# 3_Power.net
KiCad netlist of a schematic drawn in Altium Designer
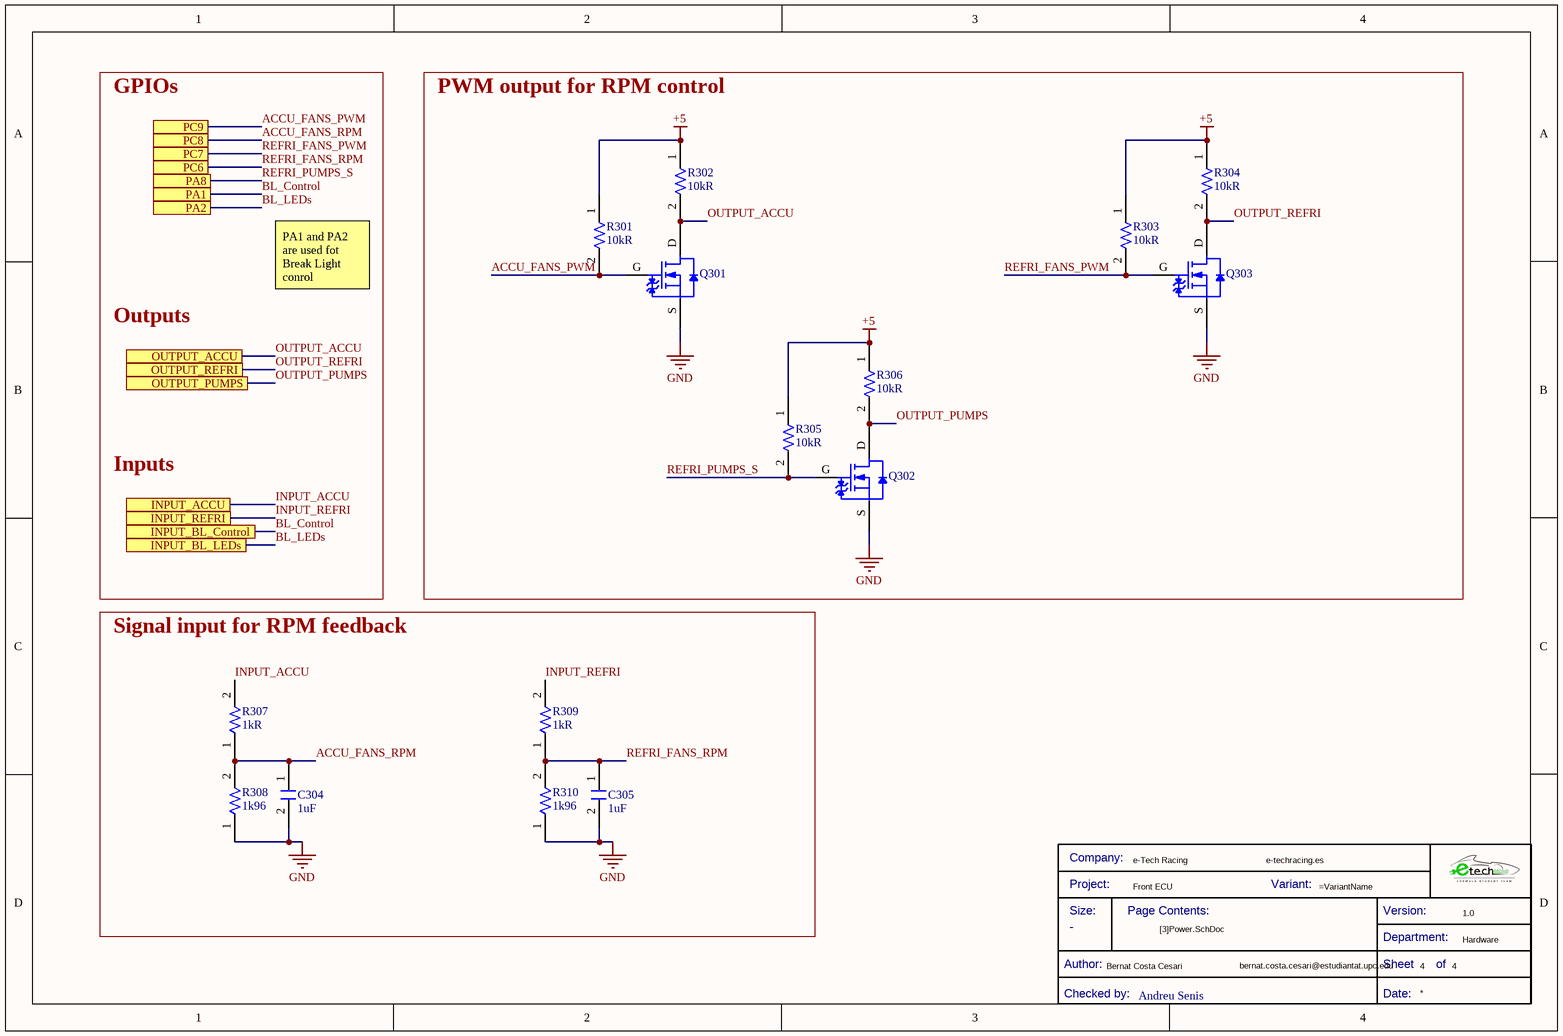
[diagram p0: [3]Power.SchDoc]

(export (version "E")
  (design (tool "Eeschema 10.0.6"))
  (components
    (comp (ref "C304")
      (value "885012207103")
      (footprint "C0805FNPC-R")
      (fields
        (field (name "TOLERANCE") "10%")
        (field (name "CAPACITANCE") "1uF")
        (field (name ".CREATOR") "GP")
      )
      (libsource (lib "Passives") (part "C1u-50V-0805FNPC-X7R"))
    )
    (comp (ref "C305")
      (value "885012207103")
      (footprint "C0805FNPC-R")
      (fields
        (field (name "TOLERANCE") "10%")
        (field (name "CAPACITANCE") "1uF")
        (field (name ".CREATOR") "GP")
      )
      (libsource (lib "Passives") (part "C1u-50V-0805FNPC-X7R"))
    )
    (comp (ref "Q301")
      (value "CPH3455-TL-H")
      (footprint "TRT-NCH-3/35-CPH")
      (description "CPH3455-TL-H N-channel MOSFET Transistor; 3 A; 35 V; 3-Pin CPH")
      (fields (field (name "MANUFACTURER") "ON Semiconductor") (field (name ".CREATOR") "GP"))
      (libsource (lib "Semiconductor") (part "TRT-NCH-3/35-CPH"))
    )
    (comp (ref "Q302")
      (value "CPH3455-TL-H")
      (footprint "TRT-NCH-3/35-CPH")
      (description "CPH3455-TL-H N-channel MOSFET Transistor; 3 A; 35 V; 3-Pin CPH")
      (fields (field (name "MANUFACTURER") "ON Semiconductor") (field (name ".CREATOR") "GP"))
      (libsource (lib "Semiconductor") (part "TRT-NCH-3/35-CPH"))
    )
    (comp (ref "Q303")
      (value "CPH3455-TL-H")
      (footprint "TRT-NCH-3/35-CPH")
      (description "CPH3455-TL-H N-channel MOSFET Transistor; 3 A; 35 V; 3-Pin CPH")
      (fields (field (name "MANUFACTURER") "ON Semiconductor") (field (name ".CREATOR") "GP"))
      (libsource (lib "Semiconductor") (part "TRT-NCH-3/35-CPH"))
    )
    (comp (ref "R301")
      (value "CR0805-JW-103ELF")
      (footprint "R0805FTK")
      (fields
        (field (name "TOLERANCE") "5%")
        (field (name "RESISTANCE") "10kR")
        (field (name ".CREATOR") "DR")
      )
      (libsource (lib "Passives") (part "R10k-0805FTK"))
    )
    (comp (ref "R302")
      (value "CR0805-JW-103ELF")
      (footprint "R0805FTK")
      (fields
        (field (name "TOLERANCE") "5%")
        (field (name "RESISTANCE") "10kR")
        (field (name ".CREATOR") "DR")
      )
      (libsource (lib "Passives") (part "R10k-0805FTK"))
    )
    (comp (ref "R303")
      (value "CR0805-JW-103ELF")
      (footprint "R0805FTK")
      (fields
        (field (name "TOLERANCE") "5%")
        (field (name "RESISTANCE") "10kR")
        (field (name ".CREATOR") "DR")
      )
      (libsource (lib "Passives") (part "R10k-0805FTK"))
    )
    (comp (ref "R304")
      (value "CR0805-JW-103ELF")
      (footprint "R0805FTK")
      (fields
        (field (name "TOLERANCE") "5%")
        (field (name "RESISTANCE") "10kR")
        (field (name ".CREATOR") "DR")
      )
      (libsource (lib "Passives") (part "R10k-0805FTK"))
    )
    (comp (ref "R305")
      (value "CR0805-JW-103ELF")
      (footprint "R0805FTK")
      (fields
        (field (name "TOLERANCE") "5%")
        (field (name "RESISTANCE") "10kR")
        (field (name ".CREATOR") "DR")
      )
      (libsource (lib "Passives") (part "R10k-0805FTK"))
    )
    (comp (ref "R306")
      (value "CR0805-JW-103ELF")
      (footprint "R0805FTK")
      (fields
        (field (name "TOLERANCE") "5%")
        (field (name "RESISTANCE") "10kR")
        (field (name ".CREATOR") "DR")
      )
      (libsource (lib "Passives") (part "R10k-0805FTK"))
    )
    (comp (ref "R307")
      (value "CR0805-JW-102ELF")
      (footprint "R0805FTK")
      (description "Res Thick Film 0805 1K Ohm 5% 1/8W ±200ppm/°C Molded SMD SMD Paper Tape on Plastic Reel")
      (fields
        (field (name "TOLERANCE") "5%")
        (field (name "RESISTANCE") "1kR")
        (field (name ".CREATOR") "GP")
      )
      (libsource (lib "Passives") (part "R1k-0805FTK"))
    )
    (comp (ref "R308")
      (value "1k96")
      (footprint "R0805FTK")
      (libsource (lib "Passives") (part "R1k96-0805FTK"))
    )
    (comp (ref "R309")
      (value "CR0805-JW-102ELF")
      (footprint "R0805FTK")
      (description "Res Thick Film 0805 1K Ohm 5% 1/8W ±200ppm/°C Molded SMD SMD Paper Tape on Plastic Reel")
      (fields
        (field (name "TOLERANCE") "5%")
        (field (name "RESISTANCE") "1kR")
        (field (name ".CREATOR") "GP")
      )
      (libsource (lib "Passives") (part "R1k-0805FTK"))
    )
    (comp (ref "R310")
      (value "1k96")
      (footprint "R0805FTK")
      (libsource (lib "Passives") (part "R1k96-0805FTK"))
    )
  )
  (nets
    (net (code "1") (name "+5") (class "Default")
      (node (ref "R301") (pin "1") (pinfunction "1_1") (pintype "passive"))
      (node (ref "R302") (pin "1") (pinfunction "1_1") (pintype "passive"))
      (node (ref "R303") (pin "1") (pinfunction "1_1") (pintype "passive"))
      (node (ref "R304") (pin "1") (pinfunction "1_1") (pintype "passive"))
      (node (ref "R305") (pin "1") (pinfunction "1_1") (pintype "passive"))
      (node (ref "R306") (pin "1") (pinfunction "1_1") (pintype "passive"))
    )
    (net (code "2") (name "/ACCU_FANS_PWM") (class "Default")
      (node (ref "Q301") (pin "G") (pinfunction "G_G") (pintype "passive"))
      (node (ref "R301") (pin "2") (pinfunction "2_2") (pintype "passive"))
    )
    (net (code "3") (name "/ACCU_FANS_RPM") (class "Default")
      (node (ref "C304") (pin "1") (pinfunction "1_1") (pintype "passive"))
      (node (ref "R307") (pin "1") (pinfunction "1_1") (pintype "passive"))
      (node (ref "R308") (pin "2") (pinfunction "2_2") (pintype "passive"))
    )
    (net (code "6") (name "/INPUT_ACCU") (class "Default")
      (node (ref "R307") (pin "2") (pinfunction "2_2") (pintype "passive"))
    )
    (net (code "7") (name "/INPUT_REFRI") (class "Default")
      (node (ref "R309") (pin "2") (pinfunction "2_2") (pintype "passive"))
    )
    (net (code "8") (name "/OUTPUT_ACCU") (class "Default")
      (node (ref "Q301") (pin "D") (pinfunction "D_D") (pintype "passive"))
      (node (ref "R302") (pin "2") (pinfunction "2_2") (pintype "passive"))
    )
    (net (code "9") (name "/OUTPUT_PUMPS") (class "Default")
      (node (ref "Q302") (pin "D") (pinfunction "D_D") (pintype "passive"))
      (node (ref "R306") (pin "2") (pinfunction "2_2") (pintype "passive"))
    )
    (net (code "10") (name "/OUTPUT_REFRI") (class "Default")
      (node (ref "Q303") (pin "D") (pinfunction "D_D") (pintype "passive"))
      (node (ref "R304") (pin "2") (pinfunction "2_2") (pintype "passive"))
    )
    (net (code "11") (name "/REFRI_FANS_PWM") (class "Default")
      (node (ref "Q303") (pin "G") (pinfunction "G_G") (pintype "passive"))
      (node (ref "R303") (pin "2") (pinfunction "2_2") (pintype "passive"))
    )
    (net (code "12") (name "/REFRI_FANS_RPM") (class "Default")
      (node (ref "C305") (pin "1") (pinfunction "1_1") (pintype "passive"))
      (node (ref "R309") (pin "1") (pinfunction "1_1") (pintype "passive"))
      (node (ref "R310") (pin "2") (pinfunction "2_2") (pintype "passive"))
    )
    (net (code "13") (name "/REFRI_PUMPS_S") (class "Default")
      (node (ref "Q302") (pin "G") (pinfunction "G_G") (pintype "passive"))
      (node (ref "R305") (pin "2") (pinfunction "2_2") (pintype "passive"))
    )
    (net (code "14") (name "GND") (class "Default")
      (node (ref "C304") (pin "2") (pinfunction "2_2") (pintype "passive"))
      (node (ref "C305") (pin "2") (pinfunction "2_2") (pintype "passive"))
      (node (ref "Q301") (pin "S") (pinfunction "S_S") (pintype "passive"))
      (node (ref "Q302") (pin "S") (pinfunction "S_S") (pintype "passive"))
      (node (ref "Q303") (pin "S") (pinfunction "S_S") (pintype "passive"))
      (node (ref "R308") (pin "1") (pinfunction "1_1") (pintype "passive"))
      (node (ref "R310") (pin "1") (pinfunction "1_1") (pintype "passive"))
    )
  )
)
